# teensy_toslink_v1_0.net
KiCad netlist of a schematic drawn in EAGLE
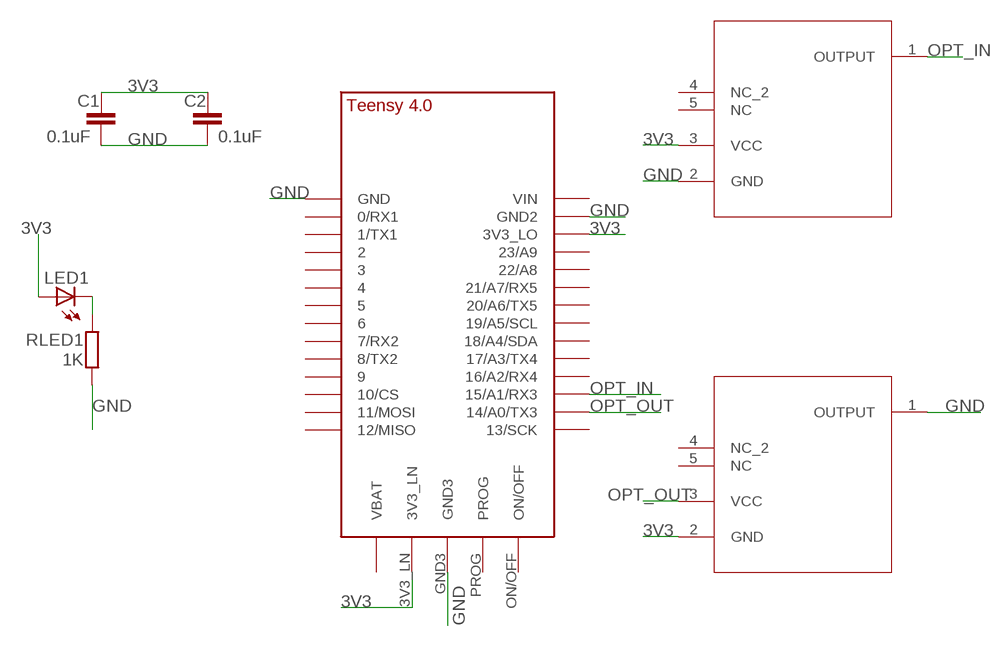
[diagram p0: schematic, sheet 1]

(export (version "E")
  (design (tool "Eeschema 10.0.6"))
  (components
    (comp (ref "C1")
      (value "0.1uF")
      (footprint "eagle-import:C0805")
      (libsource (lib "eagle-import") (part "C-EUC0805"))
    )
    (comp (ref "C2")
      (value "0.1uF")
      (footprint "eagle-import:C0805")
      (libsource (lib "eagle-import") (part "C-EUC0805"))
    )
    (comp (ref "J1")
      (value "TORX141P(F)TORX141P(F)_TOS")
      (footprint "eagle-import:TORX141P(F)_TOS")
      (fields
        (field (name "MANUFACTURER_PART_NUMBER") "TORX141P(F)")
        (field (name "COPYRIGHT") "Copyright (C) 2023 Ultra Librarian. All rights reserved.")
      )
      (libsource (lib "eagle-import") (part "TORX141P(F)TORX141P(F)_TOS"))
    )
    (comp (ref "J2")
      (value "TORX141P(F)TORX141P(F)_TOS")
      (footprint "eagle-import:TORX141P(F)_TOS")
      (fields
        (field (name "MANUFACTURER_PART_NUMBER") "TORX141P(F)")
        (field (name "COPYRIGHT") "Copyright (C) 2023 Ultra Librarian. All rights reserved.")
      )
      (libsource (lib "eagle-import") (part "TORX141P(F)TORX141P(F)_TOS"))
    )
    (comp (ref "LED1")
      (value "0805")
      (footprint "eagle-import:CHIPLED_0805")
      (libsource (lib "eagle-import") (part "LEDCHIPLED_0805"))
    )
    (comp (ref "RLED1")
      (value "1K")
      (footprint "eagle-import:R0805")
      (libsource (lib "eagle-import") (part "R-EU_R0805"))
    )
    (comp (ref "U$1")
      (value "TEENSY_4.0")
      (footprint "eagle-import:TEENSY_4.0")
      (libsource (lib "eagle-import") (part "TEENSY_4.0"))
    )
  )
  (nets
    (net (code "1") (name "/3V3") (class "Default")
      (node (ref "C1") (pin "1") (pinfunction "1_1") (pintype "passive"))
      (node (ref "C2") (pin "1") (pinfunction "1_1") (pintype "passive"))
      (node (ref "J1") (pin "3") (pinfunction "VCC_3") (pintype "power_in"))
      (node (ref "J2") (pin "2") (pinfunction "GND_2") (pintype "passive"))
      (node (ref "LED1") (pin "A") (pinfunction "A_A") (pintype "passive"))
      (node (ref "U$1") (pin "3V3_LN") (pinfunction "3V3_LN_3V3_LN") (pintype "bidirectional"))
      (node (ref "U$1") (pin "3V3_LO") (pinfunction "3V3_LO_3V3_LO") (pintype "bidirectional"))
    )
    (net (code "2") (name "/GND") (class "Default")
      (node (ref "C1") (pin "2") (pinfunction "2_2") (pintype "passive"))
      (node (ref "C2") (pin "2") (pinfunction "2_2") (pintype "passive"))
      (node (ref "J1") (pin "2") (pinfunction "GND_2") (pintype "passive"))
      (node (ref "J2") (pin "1") (pinfunction "OUTPUT_1") (pintype "output"))
      (node (ref "RLED1") (pin "1") (pinfunction "1_1") (pintype "passive"))
      (node (ref "U$1") (pin "GND") (pinfunction "GND_GND") (pintype "bidirectional"))
      (node (ref "U$1") (pin "GND2") (pinfunction "GND2_GND2") (pintype "bidirectional"))
      (node (ref "U$1") (pin "GND3") (pinfunction "GND3_GND3") (pintype "bidirectional"))
    )
    (net (code "3") (name "/OPT_IN") (class "Default")
      (node (ref "J1") (pin "1") (pinfunction "OUTPUT_1") (pintype "output"))
      (node (ref "U$1") (pin "15/A1") (pinfunction "15/A1/RX3_15/A1") (pintype "bidirectional"))
    )
    (net (code "4") (name "/OPT_OUT") (class "Default")
      (node (ref "J2") (pin "3") (pinfunction "VCC_3") (pintype "power_in"))
      (node (ref "U$1") (pin "14/A0") (pinfunction "14/A0/TX3_14/A0") (pintype "bidirectional"))
    )
    (net (code "5") (name "Net-(LED1-PadC)") (class "Default")
      (node (ref "LED1") (pin "C") (pinfunction "C_C") (pintype "passive"))
      (node (ref "RLED1") (pin "2") (pinfunction "2_2") (pintype "passive"))
    )
    (net (code "6") (name "unconnected-(J1-NC-Pad5)") (class "Default")
      (node (ref "J1") (pin "5") (pinfunction "NC_5") (pintype "no_connect"))
    )
    (net (code "7") (name "unconnected-(J1-NC_2-Pad4)") (class "Default")
      (node (ref "J1") (pin "4") (pinfunction "NC_2_4") (pintype "no_connect"))
    )
    (net (code "8") (name "unconnected-(J2-NC-Pad5)") (class "Default")
      (node (ref "J2") (pin "5") (pinfunction "NC_5") (pintype "no_connect"))
    )
    (net (code "9") (name "unconnected-(J2-NC_2-Pad4)") (class "Default")
      (node (ref "J2") (pin "4") (pinfunction "NC_2_4") (pintype "no_connect"))
    )
    (net (code "10") (name "unconnected-(U$1-0{slash}RX1-Pad0{slash}RX)") (class "Default")
      (node (ref "U$1") (pin "0/RX") (pinfunction "0/RX1_0/RX") (pintype "bidirectional"))
    )
    (net (code "11") (name "unconnected-(U$1-1{slash}TX1-Pad1{slash}TX)") (class "Default")
      (node (ref "U$1") (pin "1/TX") (pinfunction "1/TX1_1/TX") (pintype "bidirectional"))
    )
    (net (code "12") (name "unconnected-(U$1-3-Pad3{slash}CANTX)") (class "Default")
      (node (ref "U$1") (pin "3/CANTX") (pinfunction "3_3/CANTX") (pintype "bidirectional"))
    )
    (net (code "13") (name "unconnected-(U$1-4-Pad4{slash}CANRX)") (class "Default")
      (node (ref "U$1") (pin "4/CANRX") (pinfunction "4_4/CANRX") (pintype "bidirectional"))
    )
    (net (code "14") (name "unconnected-(U$1-7{slash}RX2-Pad7)") (class "Default")
      (node (ref "U$1") (pin "7") (pinfunction "7/RX2_7") (pintype "bidirectional"))
    )
    (net (code "15") (name "unconnected-(U$1-8{slash}TX2-Pad8)") (class "Default")
      (node (ref "U$1") (pin "8") (pinfunction "8/TX2_8") (pintype "bidirectional"))
    )
    (net (code "16") (name "unconnected-(U$1-9-Pad9{slash}CS)") (class "Default")
      (node (ref "U$1") (pin "9/CS") (pinfunction "9_9/CS") (pintype "bidirectional"))
    )
    (net (code "17") (name "unconnected-(U$1-16{slash}A2{slash}RX4-Pad16{slash}A2)") (class "Default")
      (node (ref "U$1") (pin "16/A2") (pinfunction "16/A2/RX4_16/A2") (pintype "bidirectional"))
    )
    (net (code "18") (name "unconnected-(U$1-17{slash}A3{slash}TX4-Pad17{slash}A3)") (class "Default")
      (node (ref "U$1") (pin "17/A3") (pinfunction "17/A3/TX4_17/A3") (pintype "bidirectional"))
    )
    (net (code "19") (name "unconnected-(U$1-20{slash}A6{slash}TX5-Pad20{slash}A6)") (class "Default")
      (node (ref "U$1") (pin "20/A6") (pinfunction "20/A6/TX5_20/A6") (pintype "bidirectional"))
    )
    (net (code "20") (name "unconnected-(U$1-21{slash}A7{slash}RX5-Pad21{slash}A7)") (class "Default")
      (node (ref "U$1") (pin "21/A7") (pinfunction "21/A7/RX5_21/A7") (pintype "bidirectional"))
    )
    (net (code "21") (name "unconnected-(U$1-Pad2)") (class "Default")
      (node (ref "U$1") (pin "2") (pinfunction "2_2") (pintype "bidirectional"))
    )
    (net (code "22") (name "unconnected-(U$1-Pad5)") (class "Default")
      (node (ref "U$1") (pin "5") (pinfunction "5_5") (pintype "bidirectional"))
    )
    (net (code "23") (name "unconnected-(U$1-Pad6)") (class "Default")
      (node (ref "U$1") (pin "6") (pinfunction "6_6") (pintype "bidirectional"))
    )
    (net (code "24") (name "unconnected-(U$1-Pad10{slash}CS)") (class "Default")
      (node (ref "U$1") (pin "10/CS") (pinfunction "10/CS_10/CS") (pintype "bidirectional"))
    )
    (net (code "25") (name "unconnected-(U$1-Pad11{slash}MOSI)") (class "Default")
      (node (ref "U$1") (pin "11/MOSI") (pinfunction "11/MOSI_11/MOSI") (pintype "bidirectional"))
    )
    (net (code "26") (name "unconnected-(U$1-Pad12{slash}MISO)") (class "Default")
      (node (ref "U$1") (pin "12/MISO") (pinfunction "12/MISO_12/MISO") (pintype "bidirectional"))
    )
    (net (code "27") (name "unconnected-(U$1-Pad13{slash}SCK)") (class "Default")
      (node (ref "U$1") (pin "13/SCK") (pinfunction "13/SCK_13/SCK") (pintype "bidirectional"))
    )
    (net (code "28") (name "unconnected-(U$1-Pad18{slash}A4{slash}SDA)") (class "Default")
      (node (ref "U$1") (pin "18/A4/SDA") (pinfunction "18/A4/SDA_18/A4/SDA") (pintype "bidirectional"))
    )
    (net (code "29") (name "unconnected-(U$1-Pad19{slash}A5{slash}SCL)") (class "Default")
      (node (ref "U$1") (pin "19/A5/SCL") (pinfunction "19/A5/SCL_19/A5/SCL") (pintype "bidirectional"))
    )
    (net (code "30") (name "unconnected-(U$1-Pad22{slash}A8)") (class "Default")
      (node (ref "U$1") (pin "22/A8") (pinfunction "22/A8_22/A8") (pintype "bidirectional"))
    )
    (net (code "31") (name "unconnected-(U$1-Pad23{slash}A9)") (class "Default")
      (node (ref "U$1") (pin "23/A9") (pinfunction "23/A9_23/A9") (pintype "bidirectional"))
    )
    (net (code "32") (name "unconnected-(U$1-PadON{slash}OFF)") (class "Default")
      (node (ref "U$1") (pin "ON/OFF") (pinfunction "ON/OFF_ON/OFF") (pintype "bidirectional"))
    )
    (net (code "33") (name "unconnected-(U$1-PadPROG)") (class "Default")
      (node (ref "U$1") (pin "PROG") (pinfunction "PROG_PROG") (pintype "bidirectional"))
    )
    (net (code "34") (name "unconnected-(U$1-PadVIN)") (class "Default")
      (node (ref "U$1") (pin "VIN") (pinfunction "VIN_VIN") (pintype "bidirectional"))
    )
    (net (code "35") (name "unconnected-(U$1-VBAT-PadVBAT\\)") (class "Default")
      (node (ref "U$1") (pin "VBAT\\") (pinfunction "VBAT_VBAT\\") (pintype "bidirectional"))
    )
  )
)
